# 5_Band_Equalizer.net
KiCad netlist of a schematic drawn in Altium Designer
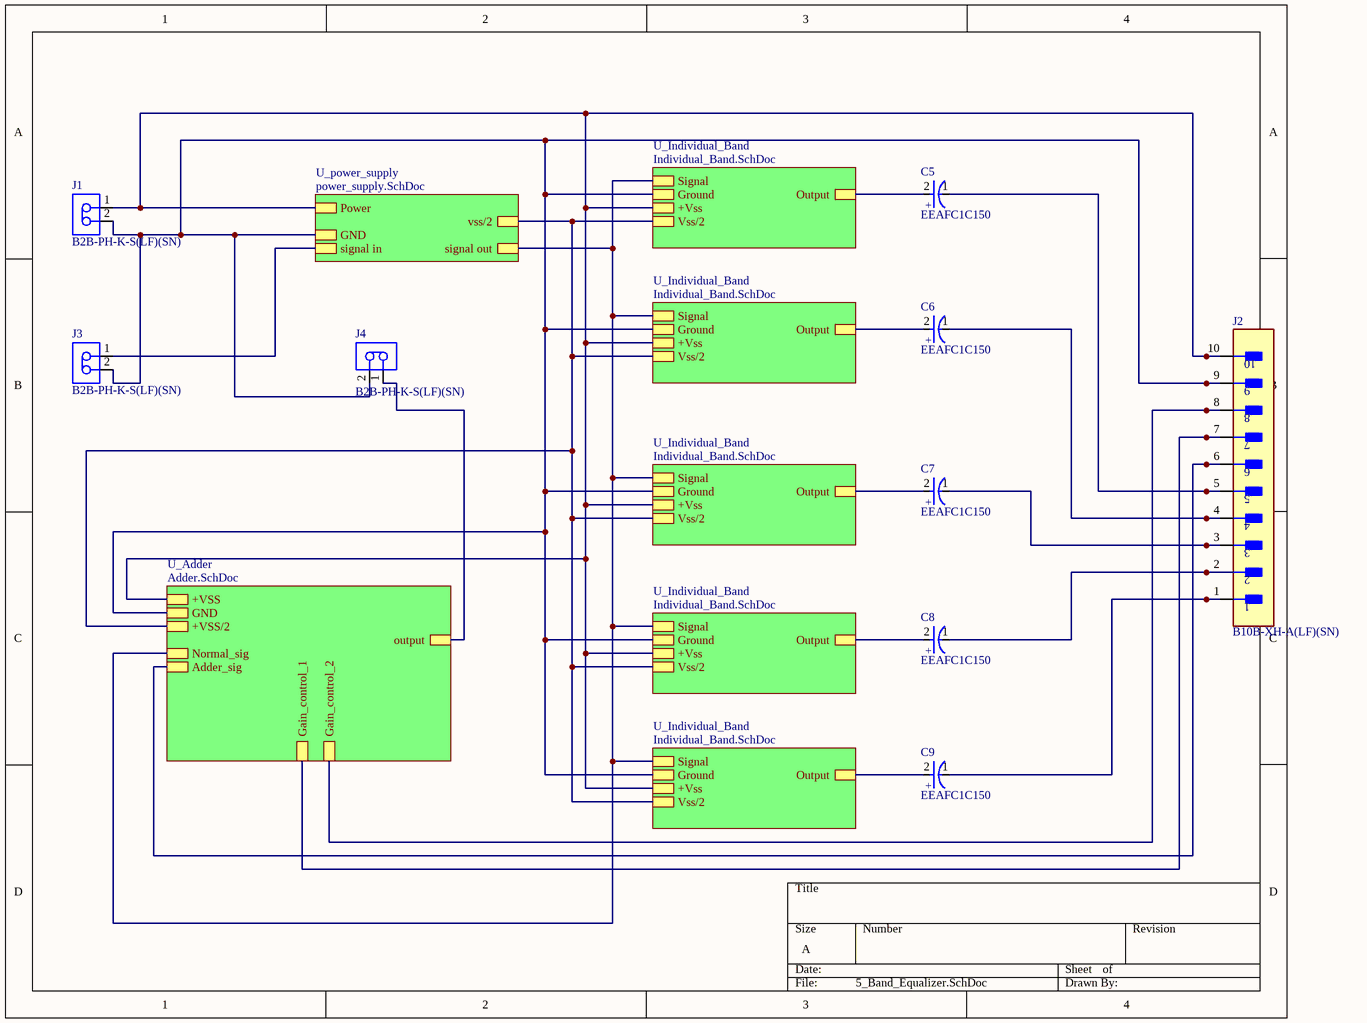
[diagram p0: 5_Band_Equalizer.SchDoc]

(export (version "E")
  (design (tool "Eeschema 10.0.6"))
  (components
    (comp (ref "C5")
      (value "EEAFC1C150")
      (footprint "FP-RAD-TH-D_4_0_5-L_7_1-F-MFG")
      (description "Aluminum Electrolytic Capacitors (Radial Lead Type) AEC-Q200 Qualified 15uF ±20% 16V")
      (fields (field (name "VOLTAGE") "16V") (field (name "TOLERANCE") "20%"))
      (libsource (lib "Altium Content Vault") (part "a00bbbee19879c290e62620ae7e47b1"))
    )
    (comp (ref "C6")
      (value "EEAFC1C150")
      (footprint "FP-RAD-TH-D_4_0_5-L_7_1-F-MFG")
      (description "Aluminum Electrolytic Capacitors (Radial Lead Type) AEC-Q200 Qualified 15uF ±20% 16V")
      (fields (field (name "VOLTAGE") "16V") (field (name "TOLERANCE") "20%"))
      (libsource (lib "Altium Content Vault") (part "a00bbbee19879c290e62620ae7e47b1"))
    )
    (comp (ref "C7")
      (value "EEAFC1C150")
      (footprint "FP-RAD-TH-D_4_0_5-L_7_1-F-MFG")
      (description "Aluminum Electrolytic Capacitors (Radial Lead Type) AEC-Q200 Qualified 15uF ±20% 16V")
      (fields (field (name "VOLTAGE") "16V") (field (name "TOLERANCE") "20%"))
      (libsource (lib "Altium Content Vault") (part "a00bbbee19879c290e62620ae7e47b1"))
    )
    (comp (ref "C8")
      (value "EEAFC1C150")
      (footprint "FP-RAD-TH-D_4_0_5-L_7_1-F-MFG")
      (description "Aluminum Electrolytic Capacitors (Radial Lead Type) AEC-Q200 Qualified 15uF ±20% 16V")
      (fields (field (name "VOLTAGE") "16V") (field (name "TOLERANCE") "20%"))
      (libsource (lib "Altium Content Vault") (part "a00bbbee19879c290e62620ae7e47b1"))
    )
    (comp (ref "C9")
      (value "EEAFC1C150")
      (footprint "FP-RAD-TH-D_4_0_5-L_7_1-F-MFG")
      (description "Aluminum Electrolytic Capacitors (Radial Lead Type) AEC-Q200 Qualified 15uF ±20% 16V")
      (fields (field (name "VOLTAGE") "16V") (field (name "TOLERANCE") "20%"))
      (libsource (lib "Altium Content Vault") (part "a00bbbee19879c290e62620ae7e47b1"))
    )
    (comp (ref "J1")
      (value "B2B-PH-K-S(LF)(SN)")
      (footprint "JST-B2B-PH-K-S_V")
      (fields (field (name "MANUFACTURER") "JST"))
      (libsource (lib "Altium Content Vault") (part "CN-2P-F-QF2"))
    )
    (comp (ref "J2")
      (value "B10B-XH-A(LF)(SN)")
      (footprint "FP-B10B-XH-A_LF_SN-MFG")
      (description "CONN HEADER VERT 10POS 2.5MM")
      (libsource (lib "Altium Content Vault") (part "aee40dc8b284c03a16094555aa210be"))
    )
    (comp (ref "J3")
      (value "B2B-PH-K-S(LF)(SN)")
      (footprint "JST-B2B-PH-K-S_V")
      (fields (field (name "MANUFACTURER") "JST"))
      (libsource (lib "Altium Content Vault") (part "CN-2P-F-QF2"))
    )
    (comp (ref "J4")
      (value "B2B-PH-K-S(LF)(SN)")
      (footprint "JST-B2B-PH-K-S_V")
      (fields (field (name "MANUFACTURER") "JST"))
      (libsource (lib "Altium Content Vault") (part "CN-2P-F-QF2"))
    )
  )
  (nets
    (net (code "1") (name "/+VSS") (class "Default")
      (node (ref "J1") (pin "1") (pinfunction "1_1") (pintype "passive"))
      (node (ref "J2") (pin "10") (pinfunction "10_10") (pintype "passive"))
    )
    (net (code "3") (name "/Adder_sig") (class "Default")
      (node (ref "J2") (pin "6") (pinfunction "6_6") (pintype "passive"))
    )
    (net (code "4") (name "/GND") (class "Default")
      (node (ref "J1") (pin "2") (pinfunction "2_2") (pintype "passive"))
      (node (ref "J2") (pin "9") (pinfunction "9_9") (pintype "passive"))
      (node (ref "J3") (pin "2") (pinfunction "2_2") (pintype "passive"))
      (node (ref "J4") (pin "2") (pinfunction "2_2") (pintype "passive"))
    )
    (net (code "5") (name "/Gain_control_1") (class "Default")
      (node (ref "J2") (pin "7") (pinfunction "7_7") (pintype "passive"))
    )
    (net (code "6") (name "/Gain_control_2") (class "Default")
      (node (ref "J2") (pin "8") (pinfunction "8_8") (pintype "passive"))
    )
    (net (code "8") (name "/Output") (class "Default")
      (node (ref "C6") (pin "2") (pinfunction "A_2") (pintype "passive"))
    )
    (net (code "9") (name "/Output_1") (class "Default")
      (node (ref "C9") (pin "2") (pinfunction "A_2") (pintype "passive"))
    )
    (net (code "10") (name "/Output_2") (class "Default")
      (node (ref "C8") (pin "2") (pinfunction "A_2") (pintype "passive"))
    )
    (net (code "11") (name "/Output_3") (class "Default")
      (node (ref "C5") (pin "2") (pinfunction "A_2") (pintype "passive"))
    )
    (net (code "12") (name "/Output_4") (class "Default")
      (node (ref "C7") (pin "2") (pinfunction "A_2") (pintype "passive"))
    )
    (net (code "13") (name "/output") (class "Default")
      (node (ref "J4") (pin "1") (pinfunction "1_1") (pintype "passive"))
    )
    (net (code "14") (name "/signal in") (class "Default")
      (node (ref "J3") (pin "1") (pinfunction "1_1") (pintype "passive"))
    )
    (net (code "15") (name "Net-(C5-C)") (class "Default")
      (node (ref "C5") (pin "1") (pinfunction "C_1") (pintype "passive"))
      (node (ref "J2") (pin "5") (pinfunction "5_5") (pintype "passive"))
    )
    (net (code "16") (name "Net-(C6-C)") (class "Default")
      (node (ref "C6") (pin "1") (pinfunction "C_1") (pintype "passive"))
      (node (ref "J2") (pin "4") (pinfunction "4_4") (pintype "passive"))
    )
    (net (code "17") (name "Net-(C7-C)") (class "Default")
      (node (ref "C7") (pin "1") (pinfunction "C_1") (pintype "passive"))
      (node (ref "J2") (pin "3") (pinfunction "3_3") (pintype "passive"))
    )
    (net (code "18") (name "Net-(C8-C)") (class "Default")
      (node (ref "C8") (pin "1") (pinfunction "C_1") (pintype "passive"))
      (node (ref "J2") (pin "2") (pinfunction "2_2") (pintype "passive"))
    )
    (net (code "19") (name "Net-(C9-C)") (class "Default")
      (node (ref "C9") (pin "1") (pinfunction "C_1") (pintype "passive"))
      (node (ref "J2") (pin "1") (pinfunction "1_1") (pintype "passive"))
    )
  )
)
